# ProPrj_5VBuck_MP2236_2024-12-13.net
KiCad netlist of a schematic drawn in EasyEDA Pro
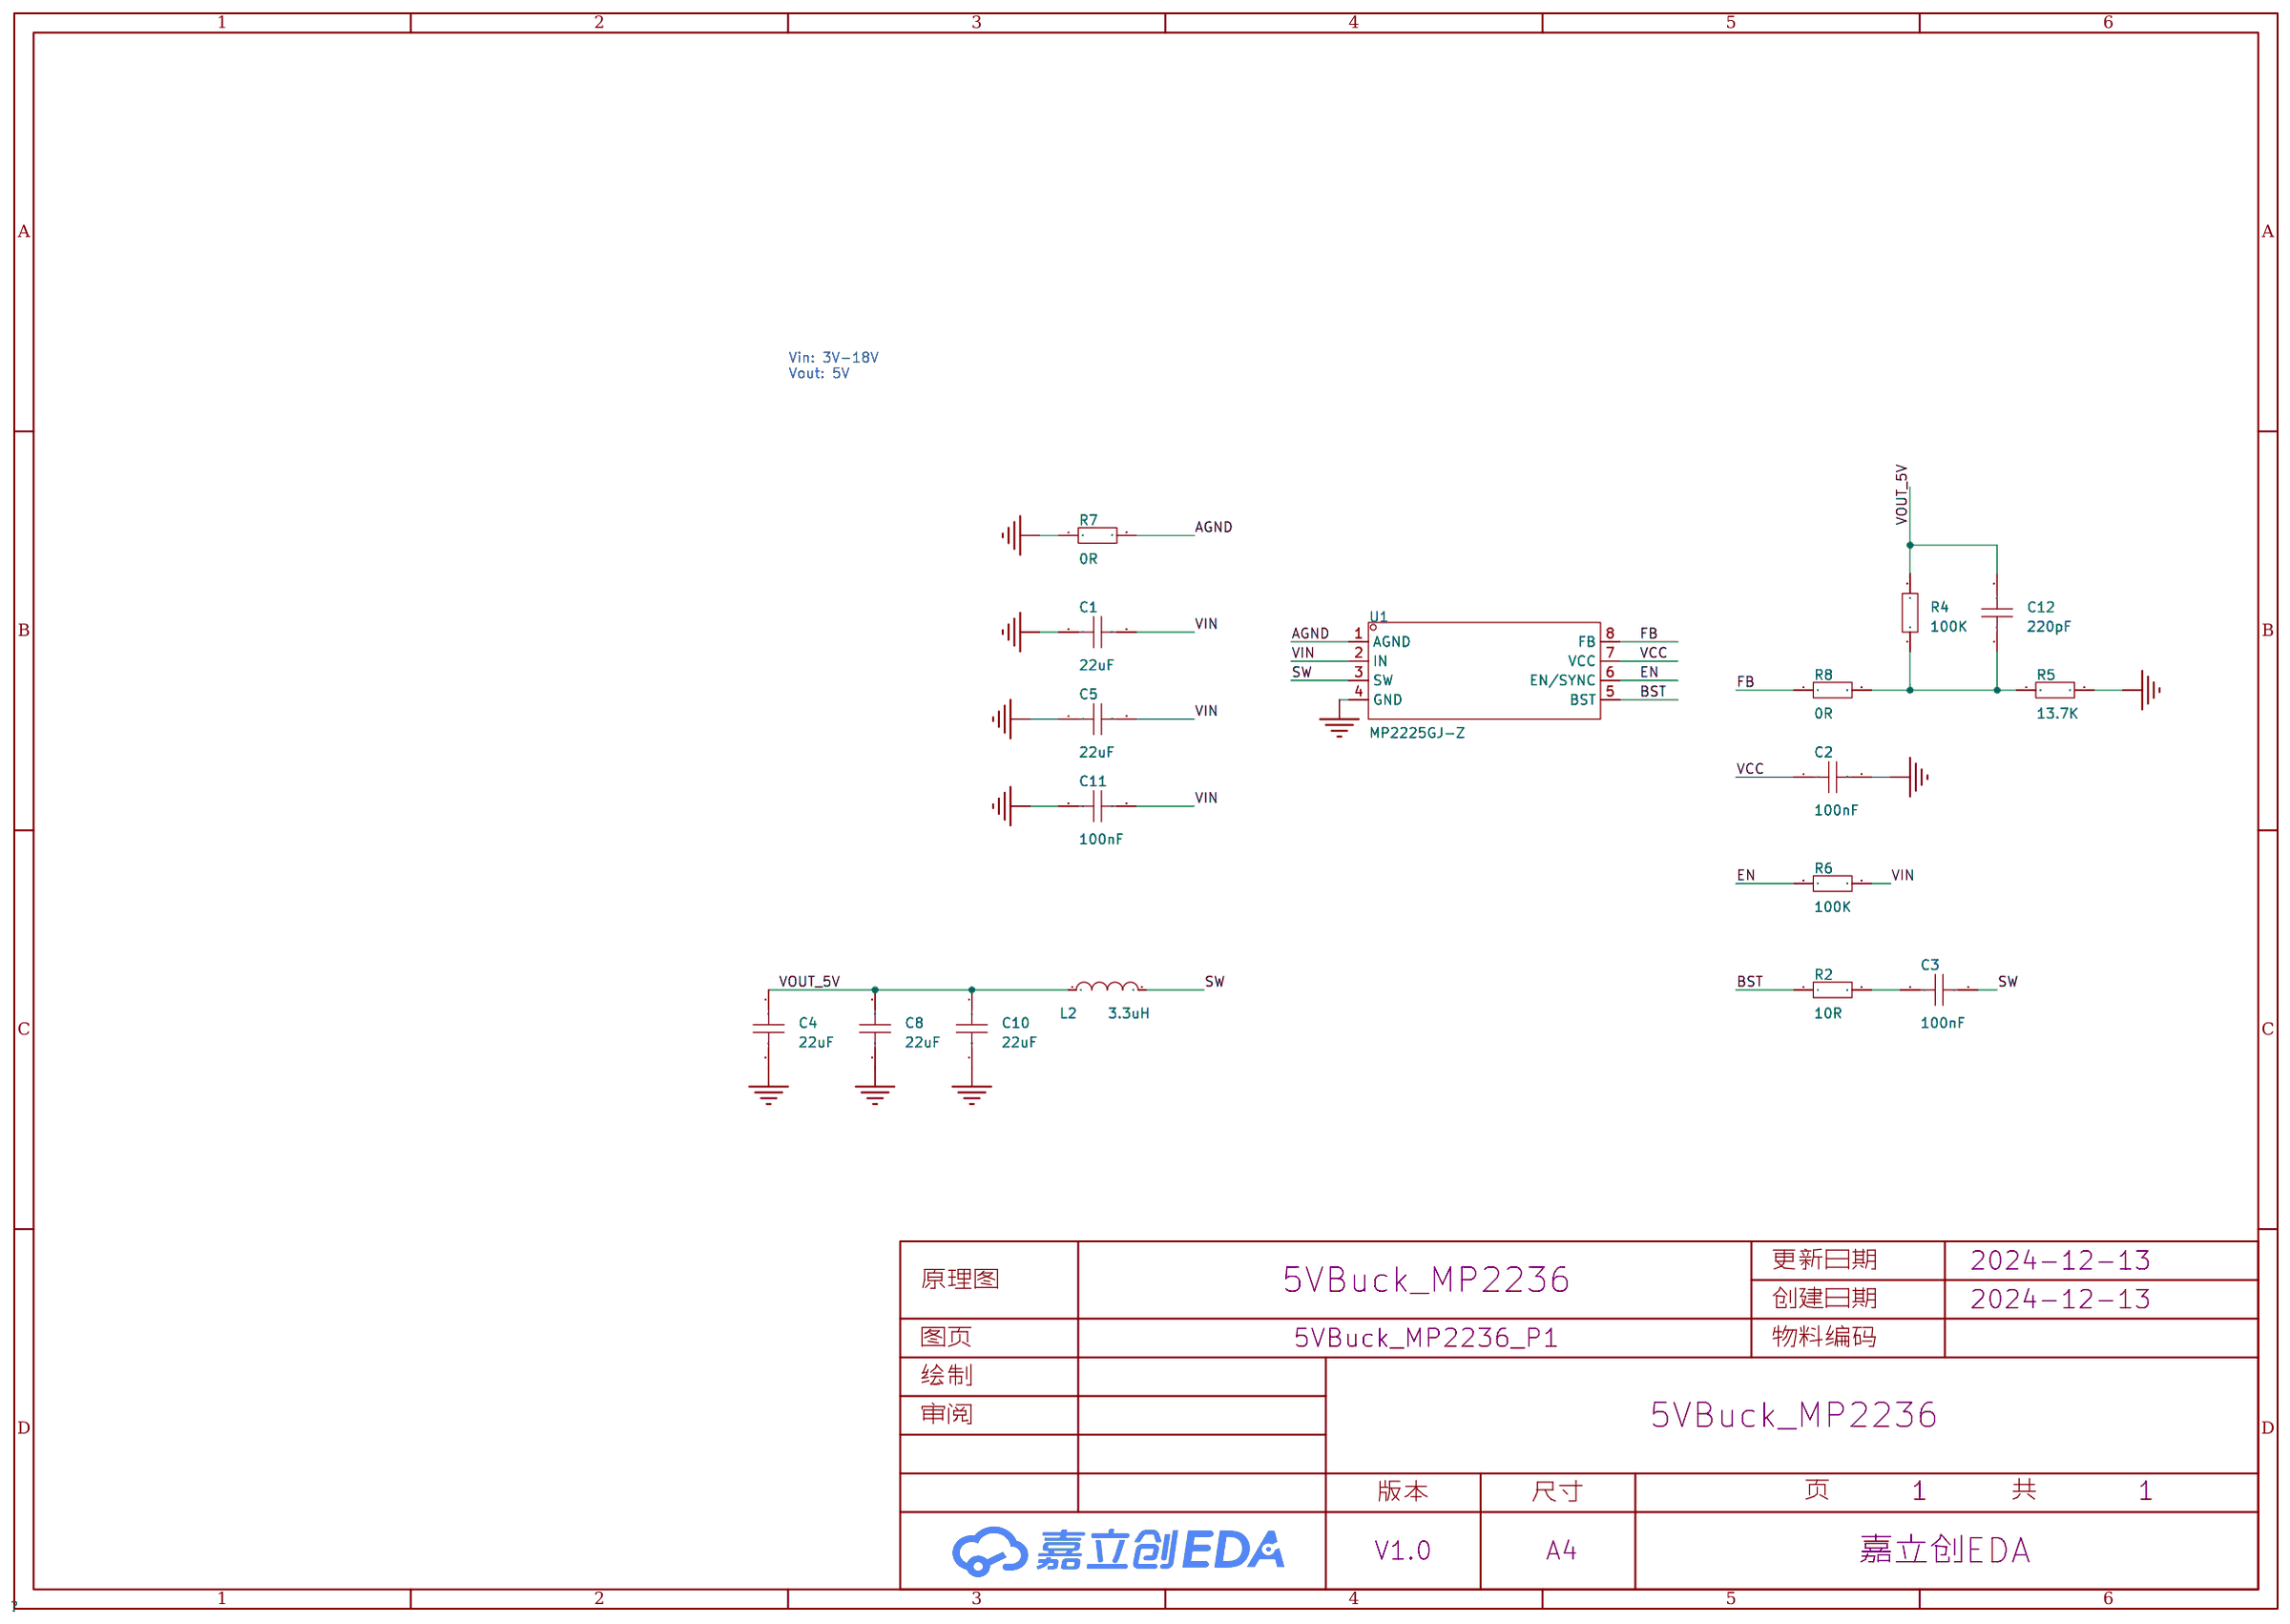
[diagram p0: schematic sheet]

(export (version "E")
  (design (tool "Eeschema 10.0.6"))
  (components
    (comp (ref "C1")
      (value "22uF")
      (footprint "easyedapro:C0805")
      (libsource (lib "easyedapro") (part "CapAcitance"))
    )
    (comp (ref "C2")
      (value "100nF")
      (footprint "easyedapro:C0805")
      (libsource (lib "easyedapro") (part "CapAcitance"))
    )
    (comp (ref "C3")
      (value "100nF")
      (footprint "easyedapro:C0805")
      (libsource (lib "easyedapro") (part "CapAcitance"))
    )
    (comp (ref "C4")
      (value "22uF")
      (footprint "easyedapro:C0805")
      (libsource (lib "easyedapro") (part "CapAcitance"))
    )
    (comp (ref "C5")
      (value "22uF")
      (footprint "easyedapro:C0805")
      (libsource (lib "easyedapro") (part "CapAcitance"))
    )
    (comp (ref "C8")
      (value "22uF")
      (footprint "easyedapro:C0805")
      (libsource (lib "easyedapro") (part "CapAcitance"))
    )
    (comp (ref "C10")
      (value "22uF")
      (footprint "easyedapro:C0805")
      (libsource (lib "easyedapro") (part "CapAcitance"))
    )
    (comp (ref "C11")
      (value "100nF")
      (footprint "easyedapro:C0805")
      (libsource (lib "easyedapro") (part "CapAcitance"))
    )
    (comp (ref "C12")
      (value "220pF")
      (footprint "easyedapro:C0805")
      (libsource (lib "easyedapro") (part "CapAcitance"))
    )
    (comp (ref "L2")
      (value "3.3uH")
      (footprint "easyedapro:IND-SMD_L7.1-W6.6_MJC-0603T")
      (description "电感值:5.6uH;精度:±20%;额定电流:5.5A;饱和电流(Isat):7A;类型:一体成型电感;")
      (fields
        (field (name "Manufacturer Part") "CXP0630-5R6M-AG(5.6uh)")
        (field (name "Manufacturer") "DMBJ(振宝佳)")
      )
      (libsource (lib "easyedapro") (part "CXP0630-5R6M-AG(5.6UH)"))
    )
    (comp (ref "R2") (value "10R") (footprint "easyedapro:R0805") (libsource (lib "easyedapro") (part "电阻")))
    (comp (ref "R4") (value "100K") (footprint "easyedapro:R0805") (libsource (lib "easyedapro") (part "电阻")))
    (comp (ref "R5")
      (value "13.7K")
      (footprint "easyedapro:R0805")
      (libsource (lib "easyedapro") (part "电阻"))
    )
    (comp (ref "R6") (value "100K") (footprint "easyedapro:R0805") (libsource (lib "easyedapro") (part "电阻")))
    (comp (ref "R7") (value "0R") (footprint "easyedapro:R0805") (libsource (lib "easyedapro") (part "电阻")))
    (comp (ref "R8") (value "0R") (footprint "easyedapro:R0805") (libsource (lib "easyedapro") (part "电阻")))
    (comp (ref "U1")
      (value "MP2225GJ-Z")
      (footprint "easyedapro:TSOT-23-8_L2.9-W1.6-P0.65-LS2.8-BR")
      (description "功能类型:降压型;输出类型:可调;输入电压:4.5V~18V;输出电压:600mV~18V;输出电流:5A;")
      (fields (field (name "Manufacturer") "MPS(芯源)"))
      (libsource (lib "easyedapro") (part "MP2225GJ-Z"))
    )
  )
  (nets
    (net (code "1") (name "/AGND") (class "Default")
      (node (ref "R7") (pin "2") (pinfunction "2_2") (pintype "input"))
      (node (ref "U1") (pin "1") (pinfunction "AGND_1") (pintype "unspecified"))
    )
    (net (code "2") (name "/BST") (class "Default")
      (node (ref "R2") (pin "1") (pinfunction "1_1") (pintype "input"))
      (node (ref "U1") (pin "5") (pinfunction "BST_5") (pintype "unspecified"))
    )
    (net (code "3") (name "/EN") (class "Default")
      (node (ref "R6") (pin "2") (pinfunction "2_2") (pintype "input"))
      (node (ref "U1") (pin "6") (pinfunction "EN/SYNC_6") (pintype "unspecified"))
    )
    (net (code "4") (name "/FB") (class "Default")
      (node (ref "R8") (pin "1") (pinfunction "1_1") (pintype "input"))
      (node (ref "U1") (pin "8") (pinfunction "FB_8") (pintype "unspecified"))
    )
    (net (code "5") (name "/SW") (class "Default")
      (node (ref "C3") (pin "2") (pinfunction "2_2") (pintype "input"))
      (node (ref "L2") (pin "2") (pinfunction "2_2") (pintype "unspecified"))
      (node (ref "U1") (pin "3") (pinfunction "SW_3") (pintype "unspecified"))
    )
    (net (code "6") (name "/VCC") (class "Default")
      (node (ref "C2") (pin "1") (pinfunction "1_1") (pintype "input"))
      (node (ref "U1") (pin "7") (pinfunction "VCC_7") (pintype "unspecified"))
    )
    (net (code "7") (name "/VIN") (class "Default")
      (node (ref "C1") (pin "2") (pinfunction "2_2") (pintype "input"))
      (node (ref "C11") (pin "2") (pinfunction "2_2") (pintype "input"))
      (node (ref "C5") (pin "2") (pinfunction "2_2") (pintype "input"))
      (node (ref "R6") (pin "1") (pinfunction "1_1") (pintype "input"))
      (node (ref "U1") (pin "2") (pinfunction "IN_2") (pintype "unspecified"))
    )
    (net (code "8") (name "/VOUT_5V") (class "Default")
      (node (ref "C10") (pin "1") (pinfunction "1_1") (pintype "input"))
      (node (ref "C12") (pin "2") (pinfunction "2_2") (pintype "input"))
      (node (ref "C4") (pin "1") (pinfunction "1_1") (pintype "input"))
      (node (ref "C8") (pin "1") (pinfunction "1_1") (pintype "input"))
      (node (ref "L2") (pin "1") (pinfunction "1_1") (pintype "unspecified"))
      (node (ref "R4") (pin "2") (pinfunction "2_2") (pintype "input"))
    )
    (net (code "9") (name "GND") (class "Default")
      (node (ref "C1") (pin "1") (pinfunction "1_1") (pintype "input"))
      (node (ref "C10") (pin "2") (pinfunction "2_2") (pintype "input"))
      (node (ref "C11") (pin "1") (pinfunction "1_1") (pintype "input"))
      (node (ref "C2") (pin "2") (pinfunction "2_2") (pintype "input"))
      (node (ref "C4") (pin "2") (pinfunction "2_2") (pintype "input"))
      (node (ref "C5") (pin "1") (pinfunction "1_1") (pintype "input"))
      (node (ref "C8") (pin "2") (pinfunction "2_2") (pintype "input"))
      (node (ref "R5") (pin "2") (pinfunction "2_2") (pintype "input"))
      (node (ref "R7") (pin "1") (pinfunction "1_1") (pintype "input"))
      (node (ref "U1") (pin "4") (pinfunction "GND_4") (pintype "unspecified"))
    )
    (net (code "10") (name "Net-(C3-Pad1)") (class "Default")
      (node (ref "C3") (pin "1") (pinfunction "1_1") (pintype "input"))
      (node (ref "R2") (pin "2") (pinfunction "2_2") (pintype "input"))
    )
    (net (code "11") (name "Net-(C12-Pad1)") (class "Default")
      (node (ref "C12") (pin "1") (pinfunction "1_1") (pintype "input"))
      (node (ref "R4") (pin "1") (pinfunction "1_1") (pintype "input"))
      (node (ref "R5") (pin "1") (pinfunction "1_1") (pintype "input"))
      (node (ref "R8") (pin "2") (pinfunction "2_2") (pintype "input"))
    )
  )
)
